# SurgicalPCB.net
KiCad netlist of a schematic drawn in EAGLE
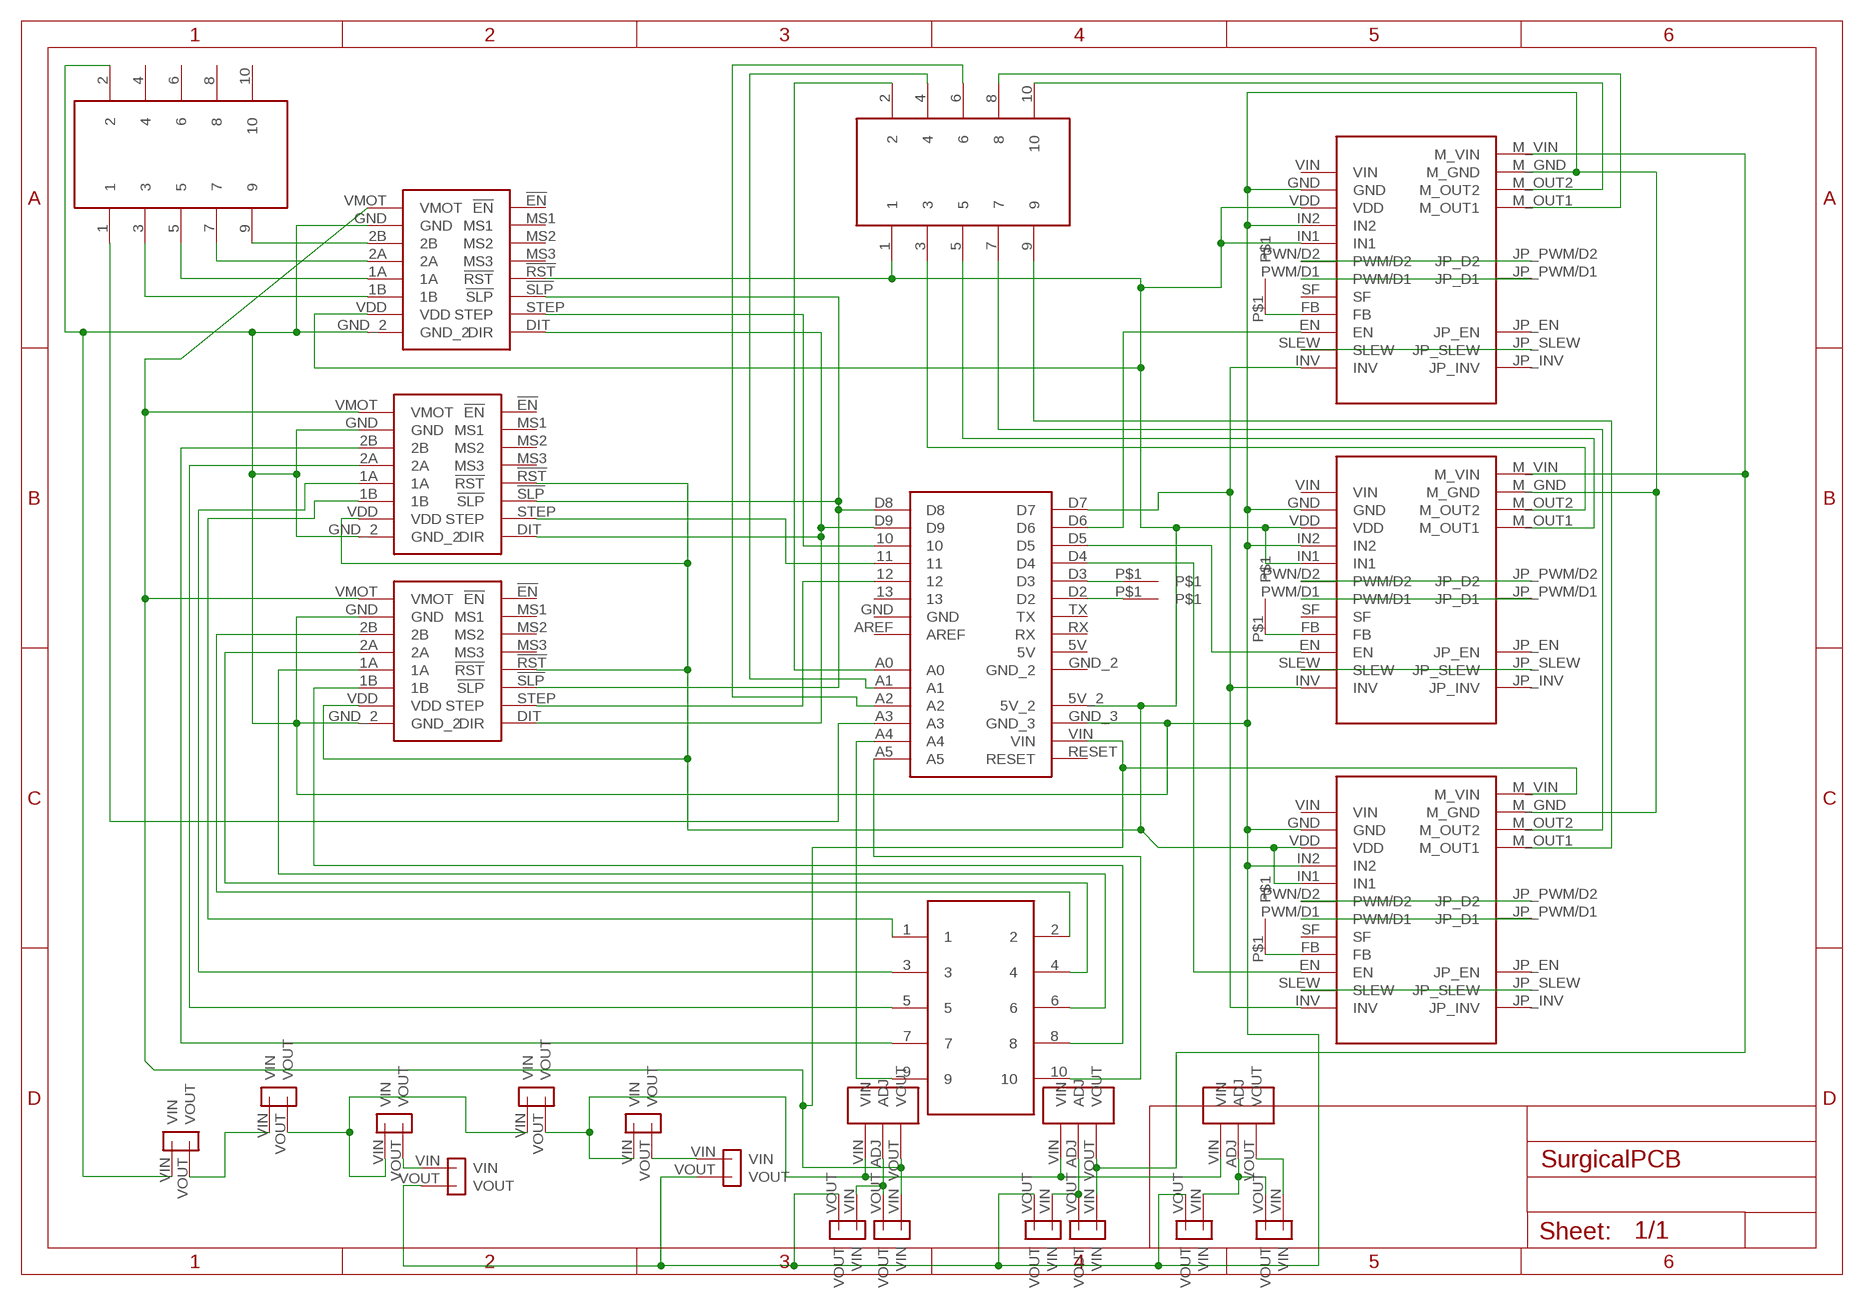
[diagram p0: schematic, sheet 1]

(export (version "E")
  (design (tool "Eeschema 10.0.6"))
  (components
    (comp (ref "6V")
      (value "V_REG")
      (footprint "eagle-import:V_REG")
      (libsource (lib "eagle-import") (part "V_REG"))
    )
    (comp (ref "10V")
      (value "V_REG")
      (footprint "eagle-import:V_REG")
      (libsource (lib "eagle-import") (part "V_REG"))
    )
    (comp (ref "EV")
      (value "V_REG")
      (footprint "eagle-import:V_REG")
      (libsource (lib "eagle-import") (part "V_REG"))
    )
    (comp (ref "E_STOP")
      (value "RESISTOR")
      (footprint "eagle-import:RESISTOR")
      (libsource (lib "eagle-import") (part "RESISTOR"))
    )
    (comp (ref "LED_GREEN")
      (value "RESISTOR")
      (footprint "eagle-import:RESISTOR")
      (libsource (lib "eagle-import") (part "RESISTOR"))
    )
    (comp (ref "LED_R")
      (value "RESISTOR")
      (footprint "eagle-import:RESISTOR")
      (libsource (lib "eagle-import") (part "RESISTOR"))
    )
    (comp (ref "LED_RES")
      (value "RESISTOR")
      (footprint "eagle-import:RESISTOR")
      (libsource (lib "eagle-import") (part "RESISTOR"))
    )
    (comp (ref "LED_RES_G")
      (value "RESISTOR")
      (footprint "eagle-import:RESISTOR")
      (libsource (lib "eagle-import") (part "RESISTOR"))
    )
    (comp (ref "POWERPLUG")
      (value "RESISTOR")
      (footprint "eagle-import:RESISTOR")
      (libsource (lib "eagle-import") (part "RESISTOR"))
    )
    (comp (ref "POWER_SWITCH")
      (value "RESISTOR")
      (footprint "eagle-import:RESISTOR")
      (libsource (lib "eagle-import") (part "RESISTOR"))
    )
    (comp (ref "RES6-1")
      (value "RESISTOR")
      (footprint "eagle-import:RESISTOR")
      (libsource (lib "eagle-import") (part "RESISTOR"))
    )
    (comp (ref "RES_6-2")
      (value "RESISTOR")
      (footprint "eagle-import:RESISTOR")
      (libsource (lib "eagle-import") (part "RESISTOR"))
    )
    (comp (ref "RES_10-1")
      (value "RESISTOR")
      (footprint "eagle-import:RESISTOR")
      (libsource (lib "eagle-import") (part "RESISTOR"))
    )
    (comp (ref "RES_10-2")
      (value "RESISTOR")
      (footprint "eagle-import:RESISTOR")
      (libsource (lib "eagle-import") (part "RESISTOR"))
    )
    (comp (ref "RES_EV-1")
      (value "RESISTOR")
      (footprint "eagle-import:RESISTOR")
      (libsource (lib "eagle-import") (part "RESISTOR"))
    )
    (comp (ref "RES_EV-2")
      (value "RESISTOR")
      (footprint "eagle-import:RESISTOR")
      (libsource (lib "eagle-import") (part "RESISTOR"))
    )
    (comp (ref "U$1")
      (value "A4955")
      (footprint "eagle-import:A4955")
      (libsource (lib "eagle-import") (part "A4955"))
    )
    (comp (ref "U$2")
      (value "A4955")
      (footprint "eagle-import:A4955")
      (libsource (lib "eagle-import") (part "A4955"))
    )
    (comp (ref "U$3")
      (value "A4955")
      (footprint "eagle-import:A4955")
      (libsource (lib "eagle-import") (part "A4955"))
    )
    (comp (ref "U$4")
      (value "BOARDUINOSTD")
      (footprint "eagle-import:BOARDUINO")
      (libsource (lib "eagle-import") (part "BOARDUINOSTD"))
    )
    (comp (ref "U$5")
      (value "MC33926")
      (footprint "eagle-import:MC33926")
      (libsource (lib "eagle-import") (part "MC33926"))
    )
    (comp (ref "U$6")
      (value "MC33926")
      (footprint "eagle-import:MC33926")
      (libsource (lib "eagle-import") (part "MC33926"))
    )
    (comp (ref "U$7")
      (value "MC33926")
      (footprint "eagle-import:MC33926")
      (libsource (lib "eagle-import") (part "MC33926"))
    )
    (comp (ref "U$8")
      (value "2_5_RIBBON")
      (footprint "eagle-import:2_5_RIBBON")
      (libsource (lib "eagle-import") (part "2_5_RIBBON"))
    )
    (comp (ref "U$9")
      (value "2_5_RIBBON")
      (footprint "eagle-import:2_5_RIBBON")
      (libsource (lib "eagle-import") (part "2_5_RIBBON"))
    )
    (comp (ref "U$10")
      (value "2_5_RIBBON")
      (footprint "eagle-import:2_5_RIBBON")
      (libsource (lib "eagle-import") (part "2_5_RIBBON"))
    )
    (comp (ref "U$14")
      (value "PROPE_HOLE")
      (footprint "eagle-import:PROPE_HOLE")
      (libsource (lib "eagle-import") (part "PROPE_HOLE"))
    )
    (comp (ref "U$23")
      (value "PROPE_HOLE")
      (footprint "eagle-import:PROPE_HOLE")
      (libsource (lib "eagle-import") (part "PROPE_HOLE"))
    )
    (comp (ref "U$24")
      (value "PROPE_HOLE")
      (footprint "eagle-import:PROPE_HOLE")
      (libsource (lib "eagle-import") (part "PROPE_HOLE"))
    )
    (comp (ref "U$25")
      (value "PROPE_HOLE")
      (footprint "eagle-import:PROPE_HOLE")
      (libsource (lib "eagle-import") (part "PROPE_HOLE"))
    )
    (comp (ref "U$26")
      (value "PROPE_HOLE")
      (footprint "eagle-import:PROPE_HOLE")
      (libsource (lib "eagle-import") (part "PROPE_HOLE"))
    )
  )
  (nets
    (net (code "1") (name "Net-(6V-PadADJ)") (class "Default")
      (node (ref "6V") (pin "ADJ") (pinfunction "ADJ_ADJ") (pintype "bidirectional"))
      (node (ref "RES6-1") (pin "VOUT") (pinfunction "VOUT_VOUT") (pintype "bidirectional"))
      (node (ref "RES_6-2") (pin "VIN") (pinfunction "VIN_VIN") (pintype "bidirectional"))
    )
    (net (code "2") (name "Net-(6V-PadVOUT)") (class "Default")
      (node (ref "6V") (pin "VOUT") (pinfunction "VOUT_VOUT") (pintype "bidirectional"))
      (node (ref "RES6-1") (pin "VIN") (pinfunction "VIN_VIN") (pintype "bidirectional"))
      (node (ref "U$5") (pin "M_VIN") (pinfunction "M_VIN_M_VIN") (pintype "bidirectional"))
      (node (ref "U$6") (pin "M_VIN") (pinfunction "M_VIN_M_VIN") (pintype "bidirectional"))
    )
    (net (code "3") (name "Net-(10V-PadADJ)") (class "Default")
      (node (ref "10V") (pin "ADJ") (pinfunction "ADJ_ADJ") (pintype "bidirectional"))
      (node (ref "RES_10-1") (pin "VOUT") (pinfunction "VOUT_VOUT") (pintype "bidirectional"))
      (node (ref "RES_10-2") (pin "VIN") (pinfunction "VIN_VIN") (pintype "bidirectional"))
    )
    (net (code "4") (name "Net-(10V-PadVIN)") (class "Default")
      (node (ref "10V") (pin "VIN") (pinfunction "VIN_VIN") (pintype "bidirectional"))
      (node (ref "6V") (pin "VIN") (pinfunction "VIN_VIN") (pintype "bidirectional"))
      (node (ref "EV") (pin "VIN") (pinfunction "VIN_VIN") (pintype "bidirectional"))
      (node (ref "E_STOP") (pin "VOUT") (pinfunction "VOUT_VOUT") (pintype "bidirectional"))
      (node (ref "LED_RES_G") (pin "VIN") (pinfunction "VIN_VIN") (pintype "bidirectional"))
    )
    (net (code "5") (name "Net-(10V-PadVOUT)") (class "Default")
      (node (ref "10V") (pin "VOUT") (pinfunction "VOUT_VOUT") (pintype "bidirectional"))
      (node (ref "RES_10-1") (pin "VIN") (pinfunction "VIN_VIN") (pintype "bidirectional"))
      (node (ref "U$1") (pin "VMOT") (pinfunction "VMOT_VMOT") (pintype "bidirectional"))
      (node (ref "U$2") (pin "VMOT") (pinfunction "VMOT_VMOT") (pintype "bidirectional"))
      (node (ref "U$3") (pin "VMOT") (pinfunction "VMOT_VMOT") (pintype "bidirectional"))
      (node (ref "U$4") (pin "VIN") (pinfunction "VIN_VIN") (pintype "bidirectional"))
      (node (ref "U$7") (pin "M_VIN") (pinfunction "M_VIN_M_VIN") (pintype "bidirectional"))
    )
    (net (code "6") (name "Net-(EV-PadADJ)") (class "Default")
      (node (ref "EV") (pin "ADJ") (pinfunction "ADJ_ADJ") (pintype "bidirectional"))
      (node (ref "RES_EV-1") (pin "VOUT") (pinfunction "VOUT_VOUT") (pintype "bidirectional"))
      (node (ref "RES_EV-2") (pin "VIN") (pinfunction "VIN_VIN") (pintype "bidirectional"))
    )
    (net (code "7") (name "Net-(EV-PadVOUT)") (class "Default")
      (node (ref "EV") (pin "VOUT") (pinfunction "VOUT_VOUT") (pintype "bidirectional"))
      (node (ref "RES_EV-1") (pin "VIN") (pinfunction "VIN_VIN") (pintype "bidirectional"))
    )
    (net (code "8") (name "Net-(E_STOP-PadVIN)") (class "Default")
      (node (ref "E_STOP") (pin "VIN") (pinfunction "VIN_VIN") (pintype "bidirectional"))
      (node (ref "LED_RES") (pin "VIN") (pinfunction "VIN_VIN") (pintype "bidirectional"))
      (node (ref "POWER_SWITCH") (pin "VOUT") (pinfunction "VOUT_VOUT") (pintype "bidirectional"))
    )
    (net (code "9") (name "Net-(LED_GREEN-PadVIN)") (class "Default")
      (node (ref "LED_GREEN") (pin "VIN") (pinfunction "VIN_VIN") (pintype "bidirectional"))
      (node (ref "LED_RES_G") (pin "VOUT") (pinfunction "VOUT_VOUT") (pintype "bidirectional"))
    )
    (net (code "10") (name "Net-(LED_GREEN-PadVOUT)") (class "Default")
      (node (ref "LED_GREEN") (pin "VOUT") (pinfunction "VOUT_VOUT") (pintype "bidirectional"))
      (node (ref "LED_R") (pin "VOUT") (pinfunction "VOUT_VOUT") (pintype "bidirectional"))
      (node (ref "POWERPLUG") (pin "VIN") (pinfunction "VIN_VIN") (pintype "bidirectional"))
      (node (ref "RES_10-2") (pin "VOUT") (pinfunction "VOUT_VOUT") (pintype "bidirectional"))
      (node (ref "RES_6-2") (pin "VOUT") (pinfunction "VOUT_VOUT") (pintype "bidirectional"))
      (node (ref "RES_EV-2") (pin "VOUT") (pinfunction "VOUT_VOUT") (pintype "bidirectional"))
      (node (ref "U$1") (pin "GND") (pinfunction "GND_GND") (pintype "bidirectional"))
      (node (ref "U$1") (pin "GND_2") (pinfunction "GND_2_GND_2") (pintype "bidirectional"))
      (node (ref "U$2") (pin "GND") (pinfunction "GND_GND") (pintype "bidirectional"))
      (node (ref "U$2") (pin "GND_2") (pinfunction "GND_2_GND_2") (pintype "bidirectional"))
      (node (ref "U$3") (pin "GND") (pinfunction "GND_GND") (pintype "bidirectional"))
      (node (ref "U$3") (pin "GND_2") (pinfunction "GND_2_GND_2") (pintype "bidirectional"))
      (node (ref "U$4") (pin "GND_3") (pinfunction "GND_3_GND_3") (pintype "bidirectional"))
      (node (ref "U$5") (pin "GND") (pinfunction "GND_GND") (pintype "bidirectional"))
      (node (ref "U$5") (pin "IN2") (pinfunction "IN2_IN2") (pintype "bidirectional"))
      (node (ref "U$5") (pin "M_GND") (pinfunction "M_GND_M_GND") (pintype "bidirectional"))
      (node (ref "U$6") (pin "GND") (pinfunction "GND_GND") (pintype "bidirectional"))
      (node (ref "U$6") (pin "IN2") (pinfunction "IN2_IN2") (pintype "bidirectional"))
      (node (ref "U$6") (pin "M_GND") (pinfunction "M_GND_M_GND") (pintype "bidirectional"))
      (node (ref "U$7") (pin "GND") (pinfunction "GND_GND") (pintype "bidirectional"))
      (node (ref "U$7") (pin "IN2") (pinfunction "IN2_IN2") (pintype "bidirectional"))
      (node (ref "U$7") (pin "M_GND") (pinfunction "M_GND_M_GND") (pintype "bidirectional"))
      (node (ref "U$9") (pin "2") (pinfunction "2_2") (pintype "bidirectional"))
    )
    (net (code "11") (name "Net-(LED_R-PadVIN)") (class "Default")
      (node (ref "LED_R") (pin "VIN") (pinfunction "VIN_VIN") (pintype "bidirectional"))
      (node (ref "LED_RES") (pin "VOUT") (pinfunction "VOUT_VOUT") (pintype "bidirectional"))
    )
    (net (code "12") (name "Net-(POWERPLUG-PadVOUT)") (class "Default")
      (node (ref "POWERPLUG") (pin "VOUT") (pinfunction "VOUT_VOUT") (pintype "bidirectional"))
      (node (ref "POWER_SWITCH") (pin "VIN") (pinfunction "VIN_VIN") (pintype "bidirectional"))
    )
    (net (code "13") (name "Net-(U$1-DIR)") (class "Default")
      (node (ref "U$1") (pin "DIT") (pinfunction "DIR_DIT") (pintype "bidirectional"))
      (node (ref "U$2") (pin "DIT") (pinfunction "DIR_DIT") (pintype "bidirectional"))
      (node (ref "U$3") (pin "DIT") (pinfunction "DIR_DIT") (pintype "bidirectional"))
      (node (ref "U$4") (pin "D9") (pinfunction "D9_D9") (pintype "bidirectional"))
    )
    (net (code "14") (name "Net-(U$1-Pad1A)") (class "Default")
      (node (ref "U$1") (pin "1A") (pinfunction "1A_1A") (pintype "bidirectional"))
      (node (ref "U$9") (pin "5") (pinfunction "5_5") (pintype "bidirectional"))
    )
    (net (code "15") (name "Net-(U$1-Pad1B)") (class "Default")
      (node (ref "U$1") (pin "1B") (pinfunction "1B_1B") (pintype "bidirectional"))
      (node (ref "U$9") (pin "3") (pinfunction "3_3") (pintype "bidirectional"))
    )
    (net (code "16") (name "Net-(U$1-Pad2A)") (class "Default")
      (node (ref "U$1") (pin "2A") (pinfunction "2A_2A") (pintype "bidirectional"))
      (node (ref "U$9") (pin "7") (pinfunction "7_7") (pintype "bidirectional"))
    )
    (net (code "17") (name "Net-(U$1-Pad2B)") (class "Default")
      (node (ref "U$1") (pin "2B") (pinfunction "2B_2B") (pintype "bidirectional"))
      (node (ref "U$9") (pin "9") (pinfunction "9_9") (pintype "bidirectional"))
    )
    (net (code "18") (name "Net-(U$1-PadSTEP)") (class "Default")
      (node (ref "U$1") (pin "STEP") (pinfunction "STEP_STEP") (pintype "bidirectional"))
      (node (ref "U$4") (pin "10") (pinfunction "10_10") (pintype "bidirectional"))
    )
    (net (code "19") (name "Net-(U$1-~{RST})") (class "Default")
      (node (ref "U$1") (pin "!RST") (pinfunction "~{RST}_!RST") (pintype "bidirectional"))
      (node (ref "U$1") (pin "VDD") (pinfunction "VDD_VDD") (pintype "bidirectional"))
      (node (ref "U$2") (pin "!RST") (pinfunction "~{RST}_!RST") (pintype "bidirectional"))
      (node (ref "U$2") (pin "VDD") (pinfunction "VDD_VDD") (pintype "bidirectional"))
      (node (ref "U$3") (pin "!RST") (pinfunction "~{RST}_!RST") (pintype "bidirectional"))
      (node (ref "U$3") (pin "VDD") (pinfunction "VDD_VDD") (pintype "bidirectional"))
      (node (ref "U$4") (pin "5V_2") (pinfunction "5V_2_5V_2") (pintype "bidirectional"))
      (node (ref "U$5") (pin "IN1") (pinfunction "IN1_IN1") (pintype "bidirectional"))
      (node (ref "U$5") (pin "VDD") (pinfunction "VDD_VDD") (pintype "bidirectional"))
      (node (ref "U$6") (pin "IN1") (pinfunction "IN1_IN1") (pintype "bidirectional"))
      (node (ref "U$6") (pin "VDD") (pinfunction "VDD_VDD") (pintype "bidirectional"))
      (node (ref "U$7") (pin "IN1") (pinfunction "IN1_IN1") (pintype "bidirectional"))
      (node (ref "U$7") (pin "VDD") (pinfunction "VDD_VDD") (pintype "bidirectional"))
      (node (ref "U$8") (pin "1") (pinfunction "1_1") (pintype "bidirectional"))
    )
    (net (code "20") (name "Net-(U$1-~{SLP})") (class "Default")
      (node (ref "U$1") (pin "!SLP") (pinfunction "~{SLP}_!SLP") (pintype "bidirectional"))
      (node (ref "U$2") (pin "!SLP") (pinfunction "~{SLP}_!SLP") (pintype "bidirectional"))
      (node (ref "U$3") (pin "!SLP") (pinfunction "~{SLP}_!SLP") (pintype "bidirectional"))
      (node (ref "U$4") (pin "D8") (pinfunction "D8_D8") (pintype "bidirectional"))
    )
    (net (code "21") (name "Net-(U$2-PadSTEP)") (class "Default")
      (node (ref "U$2") (pin "STEP") (pinfunction "STEP_STEP") (pintype "bidirectional"))
      (node (ref "U$4") (pin "11") (pinfunction "11_11") (pintype "bidirectional"))
    )
    (net (code "22") (name "Net-(U$3-PadSTEP)") (class "Default")
      (node (ref "U$3") (pin "STEP") (pinfunction "STEP_STEP") (pintype "bidirectional"))
      (node (ref "U$4") (pin "12") (pinfunction "12_12") (pintype "bidirectional"))
    )
    (net (code "23") (name "Net-(U$4-PadA0)") (class "Default")
      (node (ref "U$4") (pin "A0") (pinfunction "A0_A0") (pintype "bidirectional"))
      (node (ref "U$8") (pin "2") (pinfunction "2_2") (pintype "bidirectional"))
    )
    (net (code "24") (name "Net-(U$4-PadA1)") (class "Default")
      (node (ref "U$4") (pin "A1") (pinfunction "A1_A1") (pintype "bidirectional"))
      (node (ref "U$8") (pin "4") (pinfunction "4_4") (pintype "bidirectional"))
    )
    (net (code "25") (name "Net-(U$4-PadA2)") (class "Default")
      (node (ref "U$4") (pin "A2") (pinfunction "A2_A2") (pintype "bidirectional"))
      (node (ref "U$8") (pin "6") (pinfunction "6_6") (pintype "bidirectional"))
    )
    (net (code "26") (name "Net-(U$4-PadA3)") (class "Default")
      (node (ref "U$4") (pin "A3") (pinfunction "A3_A3") (pintype "bidirectional"))
      (node (ref "U$9") (pin "1") (pinfunction "1_1") (pintype "bidirectional"))
    )
    (net (code "27") (name "Net-(U$4-PadD4)") (class "Default")
      (node (ref "U$4") (pin "D4") (pinfunction "D4_D4") (pintype "bidirectional"))
      (node (ref "U$7") (pin "EN") (pinfunction "EN_EN") (pintype "bidirectional"))
    )
    (net (code "28") (name "Net-(U$4-PadD5)") (class "Default")
      (node (ref "U$4") (pin "D5") (pinfunction "D5_D5") (pintype "bidirectional"))
      (node (ref "U$6") (pin "EN") (pinfunction "EN_EN") (pintype "bidirectional"))
    )
    (net (code "29") (name "Net-(U$4-PadD6)") (class "Default")
      (node (ref "U$4") (pin "D6") (pinfunction "D6_D6") (pintype "bidirectional"))
      (node (ref "U$5") (pin "EN") (pinfunction "EN_EN") (pintype "bidirectional"))
    )
    (net (code "30") (name "Net-(U$4-PadD7)") (class "Default")
      (node (ref "U$4") (pin "D7") (pinfunction "D7_D7") (pintype "bidirectional"))
      (node (ref "U$5") (pin "INV") (pinfunction "INV_INV") (pintype "bidirectional"))
      (node (ref "U$6") (pin "INV") (pinfunction "INV_INV") (pintype "bidirectional"))
      (node (ref "U$7") (pin "INV") (pinfunction "INV_INV") (pintype "bidirectional"))
    )
    (net (code "31") (name "Net-(U$5-JP_D1)") (class "Default")
      (node (ref "U$5") (pin "JP_PWM/D1") (pinfunction "JP_D1_JP_PWM/D1") (pintype "bidirectional"))
      (node (ref "U$5") (pin "PWM/D1") (pinfunction "PWM/D1_PWM/D1") (pintype "bidirectional"))
    )
    (net (code "32") (name "Net-(U$5-JP_D2)") (class "Default")
      (node (ref "U$5") (pin "JP_PWM/D2") (pinfunction "JP_D2_JP_PWM/D2") (pintype "bidirectional"))
      (node (ref "U$5") (pin "PWN/D2") (pinfunction "PWM/D2_PWN/D2") (pintype "bidirectional"))
    )
    (net (code "33") (name "Net-(U$5-PadJP_SLEW)") (class "Default")
      (node (ref "U$5") (pin "JP_SLEW") (pinfunction "JP_SLEW_JP_SLEW") (pintype "bidirectional"))
      (node (ref "U$5") (pin "SLEW") (pinfunction "SLEW_SLEW") (pintype "bidirectional"))
    )
    (net (code "34") (name "Net-(U$5-PadM_OUT1)") (class "Default")
      (node (ref "U$5") (pin "M_OUT1") (pinfunction "M_OUT1_M_OUT1") (pintype "bidirectional"))
      (node (ref "U$8") (pin "8") (pinfunction "8_8") (pintype "bidirectional"))
    )
    (net (code "35") (name "Net-(U$5-PadM_OUT2)") (class "Default")
      (node (ref "U$5") (pin "M_OUT2") (pinfunction "M_OUT2_M_OUT2") (pintype "bidirectional"))
      (node (ref "U$8") (pin "10") (pinfunction "10_10") (pintype "bidirectional"))
    )
    (net (code "36") (name "Net-(U$6-JP_D1)") (class "Default")
      (node (ref "U$6") (pin "JP_PWM/D1") (pinfunction "JP_D1_JP_PWM/D1") (pintype "bidirectional"))
      (node (ref "U$6") (pin "PWM/D1") (pinfunction "PWM/D1_PWM/D1") (pintype "bidirectional"))
    )
    (net (code "37") (name "Net-(U$6-JP_D2)") (class "Default")
      (node (ref "U$6") (pin "JP_PWM/D2") (pinfunction "JP_D2_JP_PWM/D2") (pintype "bidirectional"))
      (node (ref "U$6") (pin "PWN/D2") (pinfunction "PWM/D2_PWN/D2") (pintype "bidirectional"))
    )
    (net (code "38") (name "Net-(U$6-PadJP_SLEW)") (class "Default")
      (node (ref "U$6") (pin "JP_SLEW") (pinfunction "JP_SLEW_JP_SLEW") (pintype "bidirectional"))
      (node (ref "U$6") (pin "SLEW") (pinfunction "SLEW_SLEW") (pintype "bidirectional"))
    )
    (net (code "39") (name "Net-(U$6-PadM_OUT1)") (class "Default")
      (node (ref "U$6") (pin "M_OUT1") (pinfunction "M_OUT1_M_OUT1") (pintype "bidirectional"))
      (node (ref "U$8") (pin "5") (pinfunction "5_5") (pintype "bidirectional"))
    )
    (net (code "40") (name "Net-(U$6-PadM_OUT2)") (class "Default")
      (node (ref "U$6") (pin "M_OUT2") (pinfunction "M_OUT2_M_OUT2") (pintype "bidirectional"))
      (node (ref "U$8") (pin "3") (pinfunction "3_3") (pintype "bidirectional"))
    )
    (net (code "41") (name "Net-(U$7-JP_D1)") (class "Default")
      (node (ref "U$7") (pin "JP_PWM/D1") (pinfunction "JP_D1_JP_PWM/D1") (pintype "bidirectional"))
      (node (ref "U$7") (pin "PWM/D1") (pinfunction "PWM/D1_PWM/D1") (pintype "bidirectional"))
    )
    (net (code "42") (name "Net-(U$7-JP_D2)") (class "Default")
      (node (ref "U$7") (pin "JP_PWM/D2") (pinfunction "JP_D2_JP_PWM/D2") (pintype "bidirectional"))
      (node (ref "U$7") (pin "PWN/D2") (pinfunction "PWM/D2_PWN/D2") (pintype "bidirectional"))
    )
    (net (code "43") (name "Net-(U$7-PadJP_SLEW)") (class "Default")
      (node (ref "U$7") (pin "JP_SLEW") (pinfunction "JP_SLEW_JP_SLEW") (pintype "bidirectional"))
      (node (ref "U$7") (pin "SLEW") (pinfunction "SLEW_SLEW") (pintype "bidirectional"))
    )
    (net (code "44") (name "Net-(U$7-PadM_OUT1)") (class "Default")
      (node (ref "U$7") (pin "M_OUT1") (pinfunction "M_OUT1_M_OUT1") (pintype "bidirectional"))
      (node (ref "U$8") (pin "9") (pinfunction "9_9") (pintype "bidirectional"))
    )
    (net (code "45") (name "Net-(U$7-PadM_OUT2)") (class "Default")
      (node (ref "U$7") (pin "M_OUT2") (pinfunction "M_OUT2_M_OUT2") (pintype "bidirectional"))
      (node (ref "U$8") (pin "7") (pinfunction "7_7") (pintype "bidirectional"))
    )
    (net (code "46") (name "Net-(U$10-Pad1)") (class "Default")
      (node (ref "U$10") (pin "1") (pinfunction "1_1") (pintype "bidirectional"))
      (node (ref "U$2") (pin "1B") (pinfunction "1B_1B") (pintype "bidirectional"))
    )
    (net (code "47") (name "Net-(U$10-Pad2)") (class "Default")
      (node (ref "U$10") (pin "2") (pinfunction "2_2") (pintype "bidirectional"))
      (node (ref "U$3") (pin "2B") (pinfunction "2B_2B") (pintype "bidirectional"))
    )
    (net (code "48") (name "Net-(U$10-Pad3)") (class "Default")
      (node (ref "U$10") (pin "3") (pinfunction "3_3") (pintype "bidirectional"))
      (node (ref "U$2") (pin "1A") (pinfunction "1A_1A") (pintype "bidirectional"))
    )
    (net (code "49") (name "Net-(U$10-Pad4)") (class "Default")
      (node (ref "U$10") (pin "4") (pinfunction "4_4") (pintype "bidirectional"))
      (node (ref "U$3") (pin "2A") (pinfunction "2A_2A") (pintype "bidirectional"))
    )
    (net (code "50") (name "Net-(U$10-Pad5)") (class "Default")
      (node (ref "U$10") (pin "5") (pinfunction "5_5") (pintype "bidirectional"))
      (node (ref "U$2") (pin "2A") (pinfunction "2A_2A") (pintype "bidirectional"))
    )
    (net (code "51") (name "Net-(U$10-Pad6)") (class "Default")
      (node (ref "U$10") (pin "6") (pinfunction "6_6") (pintype "bidirectional"))
      (node (ref "U$3") (pin "1A") (pinfunction "1A_1A") (pintype "bidirectional"))
    )
    (net (code "52") (name "Net-(U$10-Pad7)") (class "Default")
      (node (ref "U$10") (pin "7") (pinfunction "7_7") (pintype "bidirectional"))
      (node (ref "U$2") (pin "2B") (pinfunction "2B_2B") (pintype "bidirectional"))
    )
    (net (code "53") (name "Net-(U$10-Pad8)") (class "Default")
      (node (ref "U$10") (pin "8") (pinfunction "8_8") (pintype "bidirectional"))
      (node (ref "U$3") (pin "1B") (pinfunction "1B_1B") (pintype "bidirectional"))
    )
    (net (code "54") (name "Net-(U$10-Pad9)") (class "Default")
      (node (ref "U$10") (pin "9") (pinfunction "9_9") (pintype "bidirectional"))
      (node (ref "U$4") (pin "A4") (pinfunction "A4_A4") (pintype "bidirectional"))
    )
    (net (code "55") (name "Net-(U$10-Pad10)") (class "Default")
      (node (ref "U$10") (pin "10") (pinfunction "10_10") (pintype "bidirectional"))
      (node (ref "U$4") (pin "A5") (pinfunction "A5_A5") (pintype "bidirectional"))
    )
    (net (code "56") (name "Net-(U$14-PadP$1)") (class "Default")
      (node (ref "U$14") (pin "P$1") (pinfunction "P$1_P$1") (pintype "bidirectional"))
      (node (ref "U$7") (pin "FB") (pinfunction "FB_FB") (pintype "bidirectional"))
    )
    (net (code "57") (name "Net-(U$23-PadP$1)") (class "Default")
      (node (ref "U$23") (pin "P$1") (pinfunction "P$1_P$1") (pintype "bidirectional"))
      (node (ref "U$6") (pin "FB") (pinfunction "FB_FB") (pintype "bidirectional"))
    )
    (net (code "58") (name "Net-(U$24-PadP$1)") (class "Default")
      (node (ref "U$24") (pin "P$1") (pinfunction "P$1_P$1") (pintype "bidirectional"))
      (node (ref "U$5") (pin "FB") (pinfunction "FB_FB") (pintype "bidirectional"))
    )
    (net (code "59") (name "Net-(U$25-PadP$1)") (class "Default")
      (node (ref "U$25") (pin "P$1") (pinfunction "P$1_P$1") (pintype "bidirectional"))
      (node (ref "U$4") (pin "D3") (pinfunction "D3_D3") (pintype "bidirectional"))
    )
    (net (code "60") (name "Net-(U$26-PadP$1)") (class "Default")
      (node (ref "U$26") (pin "P$1") (pinfunction "P$1_P$1") (pintype "bidirectional"))
      (node (ref "U$4") (pin "D2") (pinfunction "D2_D2") (pintype "bidirectional"))
    )
    (net (code "61") (name "unconnected-(U$1-PadMS1)") (class "Default")
      (node (ref "U$1") (pin "MS1") (pinfunction "MS1_MS1") (pintype "bidirectional"))
    )
    (net (code "62") (name "unconnected-(U$1-PadMS2)") (class "Default")
      (node (ref "U$1") (pin "MS2") (pinfunction "MS2_MS2") (pintype "bidirectional"))
    )
    (net (code "63") (name "unconnected-(U$1-PadMS3)") (class "Default")
      (node (ref "U$1") (pin "MS3") (pinfunction "MS3_MS3") (pintype "bidirectional"))
    )
    (net (code "64") (name "unconnected-(U$1-~{EN}-Pad!EN)") (class "Default")
      (node (ref "U$1") (pin "!EN") (pinfunction "~{EN}_!EN") (pintype "bidirectional"))
    )
    (net (code "65") (name "unconnected-(U$2-PadMS1)") (class "Default")
      (node (ref "U$2") (pin "MS1") (pinfunction "MS1_MS1") (pintype "bidirectional"))
    )
    (net (code "66") (name "unconnected-(U$2-PadMS2)") (class "Default")
      (node (ref "U$2") (pin "MS2") (pinfunction "MS2_MS2") (pintype "bidirectional"))
    )
    (net (code "67") (name "unconnected-(U$2-PadMS3)") (class "Default")
      (node (ref "U$2") (pin "MS3") (pinfunction "MS3_MS3") (pintype "bidirectional"))
    )
    (net (code "68") (name "unconnected-(U$2-~{EN}-Pad!EN)") (class "Default")
      (node (ref "U$2") (pin "!EN") (pinfunction "~{EN}_!EN") (pintype "bidirectional"))
    )
    (net (code "69") (name "unconnected-(U$3-PadMS1)") (class "Default")
      (node (ref "U$3") (pin "MS1") (pinfunction "MS1_MS1") (pintype "bidirectional"))
    )
    (net (code "70") (name "unconnected-(U$3-PadMS2)") (class "Default")
      (node (ref "U$3") (pin "MS2") (pinfunction "MS2_MS2") (pintype "bidirectional"))
    )
    (net (code "71") (name "unconnected-(U$3-PadMS3)") (class "Default")
      (node (ref "U$3") (pin "MS3") (pinfunction "MS3_MS3") (pintype "bidirectional"))
    )
    (net (code "72") (name "unconnected-(U$3-~{EN}-Pad!EN)") (class "Default")
      (node (ref "U$3") (pin "!EN") (pinfunction "~{EN}_!EN") (pintype "bidirectional"))
    )
    (net (code "73") (name "unconnected-(U$4-Pad5V)") (class "Default")
      (node (ref "U$4") (pin "5V") (pinfunction "5V_5V") (pintype "bidirectional"))
    )
    (net (code "74") (name "unconnected-(U$4-Pad13)") (class "Default")
      (node (ref "U$4") (pin "13") (pinfunction "13_13") (pintype "bidirectional"))
    )
    (net (code "75") (name "unconnected-(U$4-PadAREF)") (class "Default")
      (node (ref "U$4") (pin "AREF") (pinfunction "AREF_AREF") (pintype "bidirectional"))
    )
    (net (code "76") (name "unconnected-(U$4-PadGND)") (class "Default")
      (node (ref "U$4") (pin "GND") (pinfunction "GND_GND") (pintype "bidirectional"))
    )
    (net (code "77") (name "unconnected-(U$4-PadGND_2)") (class "Default")
      (node (ref "U$4") (pin "GND_2") (pinfunction "GND_2_GND_2") (pintype "bidirectional"))
    )
    (net (code "78") (name "unconnected-(U$4-PadRESET)") (class "Default")
      (node (ref "U$4") (pin "RESET") (pinfunction "RESET_RESET") (pintype "bidirectional"))
    )
    (net (code "79") (name "unconnected-(U$4-PadRX)") (class "Default")
      (node (ref "U$4") (pin "RX") (pinfunction "RX_RX") (pintype "bidirectional"))
    )
    (net (code "80") (name "unconnected-(U$4-PadTX)") (class "Default")
      (node (ref "U$4") (pin "TX") (pinfunction "TX_TX") (pintype "bidirectional"))
    )
    (net (code "81") (name "unconnected-(U$5-PadJP_EN)") (class "Default")
      (node (ref "U$5") (pin "JP_EN") (pinfunction "JP_EN_JP_EN") (pintype "bidirectional"))
    )
    (net (code "82") (name "unconnected-(U$5-PadJP_INV)") (class "Default")
      (node (ref "U$5") (pin "JP_INV") (pinfunction "JP_INV_JP_INV") (pintype "bidirectional"))
    )
    (net (code "83") (name "unconnected-(U$5-PadSF)") (class "Default")
      (node (ref "U$5") (pin "SF") (pinfunction "SF_SF") (pintype "bidirectional"))
    )
    (net (code "84") (name "unconnected-(U$5-PadVIN)") (class "Default")
      (node (ref "U$5") (pin "VIN") (pinfunction "VIN_VIN") (pintype "bidirectional"))
    )
    (net (code "85") (name "unconnected-(U$6-PadJP_EN)") (class "Default")
      (node (ref "U$6") (pin "JP_EN") (pinfunction "JP_EN_JP_EN") (pintype "bidirectional"))
    )
    (net (code "86") (name "unconnected-(U$6-PadJP_INV)") (class "Default")
      (node (ref "U$6") (pin "JP_INV") (pinfunction "JP_INV_JP_INV") (pintype "bidirectional"))
    )
    (net (code "87") (name "unconnected-(U$6-PadSF)") (class "Default")
      (node (ref "U$6") (pin "SF") (pinfunction "SF_SF") (pintype "bidirectional"))
    )
    (net (code "88") (name "unconnected-(U$6-PadVIN)") (class "Default")
      (node (ref "U$6") (pin "VIN") (pinfunction "VIN_VIN") (pintype "bidirectional"))
    )
    (net (code "89") (name "unconnected-(U$7-PadJP_EN)") (class "Default")
      (node (ref "U$7") (pin "JP_EN") (pinfunction "JP_EN_JP_EN") (pintype "bidirectional"))
    )
    (net (code "90") (name "unconnected-(U$7-PadJP_INV)") (class "Default")
      (node (ref "U$7") (pin "JP_INV") (pinfunction "JP_INV_JP_INV") (pintype "bidirectional"))
    )
    (net (code "91") (name "unconnected-(U$7-PadSF)") (class "Default")
      (node (ref "U$7") (pin "SF") (pinfunction "SF_SF") (pintype "bidirectional"))
    )
    (net (code "92") (name "unconnected-(U$7-PadVIN)") (class "Default")
      (node (ref "U$7") (pin "VIN") (pinfunction "VIN_VIN") (pintype "bidirectional"))
    )
    (net (code "93") (name "unconnected-(U$9-Pad4)") (class "Default")
      (node (ref "U$9") (pin "4") (pinfunction "4_4") (pintype "bidirectional"))
    )
    (net (code "94") (name "unconnected-(U$9-Pad6)") (class "Default")
      (node (ref "U$9") (pin "6") (pinfunction "6_6") (pintype "bidirectional"))
    )
    (net (code "95") (name "unconnected-(U$9-Pad8)") (class "Default")
      (node (ref "U$9") (pin "8") (pinfunction "8_8") (pintype "bidirectional"))
    )
    (net (code "96") (name "unconnected-(U$9-Pad10)") (class "Default")
      (node (ref "U$9") (pin "10") (pinfunction "10_10") (pintype "bidirectional"))
    )
  )
)
